# scanline-thin.net
KiCad netlist of a schematic drawn in Altium Designer
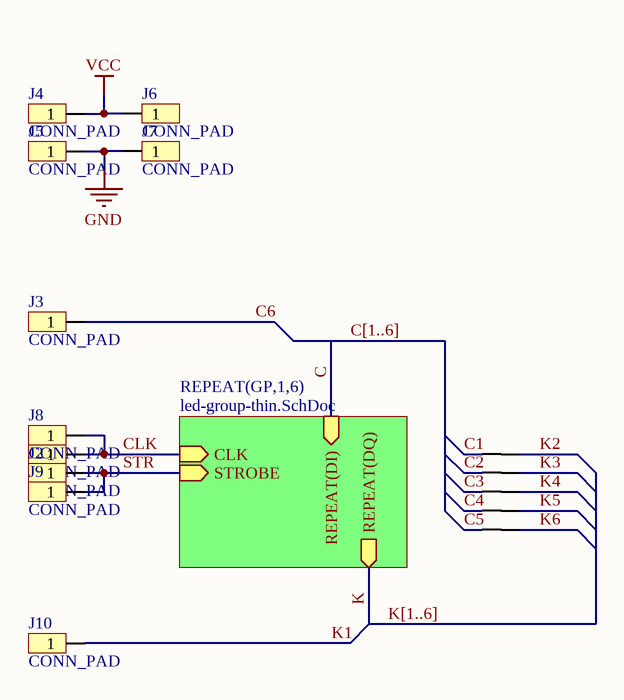
[diagram p0: scanline-thin.SchDoc]

(export (version "E")
  (design (tool "Eeschema 10.0.6"))
  (components
    (comp (ref "J1") (value "CONN_PAD") (libsource (lib "") (part "CONN_PAD_1")))
    (comp (ref "J2") (value "CONN_PAD") (libsource (lib "") (part "CONN_PAD_1")))
    (comp (ref "J3") (value "CONN_PAD") (libsource (lib "") (part "CONN_PAD_1")))
    (comp (ref "J4") (value "CONN_PAD") (libsource (lib "") (part "CONN_PAD_1")))
    (comp (ref "J5") (value "CONN_PAD") (libsource (lib "") (part "CONN_PAD_1")))
    (comp (ref "J6") (value "CONN_PAD") (libsource (lib "Components") (part "CONN_PAD")))
    (comp (ref "J7") (value "CONN_PAD") (libsource (lib "Components") (part "CONN_PAD")))
    (comp (ref "J8") (value "CONN_PAD") (libsource (lib "") (part "CONN_PAD_1")))
    (comp (ref "J9") (value "CONN_PAD") (libsource (lib "") (part "CONN_PAD_1")))
    (comp (ref "J10") (value "CONN_PAD") (libsource (lib "") (part "CONN_PAD_1")))
    (comp (ref "T2") (value "NETTIE") (footprint "NETTIE") (libsource (lib "Components") (part "NETTIE")))
    (comp (ref "T3") (value "NETTIE") (footprint "NETTIE") (libsource (lib "Components") (part "NETTIE")))
    (comp (ref "T4") (value "NETTIE") (footprint "NETTIE") (libsource (lib "Components") (part "NETTIE")))
    (comp (ref "T5") (value "NETTIE") (footprint "NETTIE") (libsource (lib "Components") (part "NETTIE")))
    (comp (ref "T6") (value "NETTIE") (footprint "NETTIE") (libsource (lib "Components") (part "NETTIE")))
  )
  (nets
    (net (code "2") (name "/C1") (class "Default")
      (node (ref "T2") (pin "1") (pinfunction "1_1") (pintype "bidirectional"))
    )
    (net (code "3") (name "/C2") (class "Default")
      (node (ref "T3") (pin "1") (pinfunction "1_1") (pintype "bidirectional"))
    )
    (net (code "4") (name "/C3") (class "Default")
      (node (ref "T4") (pin "1") (pinfunction "1_1") (pintype "bidirectional"))
    )
    (net (code "5") (name "/C4") (class "Default")
      (node (ref "T5") (pin "1") (pinfunction "1_1") (pintype "bidirectional"))
    )
    (net (code "6") (name "/C5") (class "Default")
      (node (ref "T6") (pin "1") (pinfunction "1_1") (pintype "bidirectional"))
    )
    (net (code "7") (name "/C6") (class "Default")
      (node (ref "J3") (pin "1") (pinfunction "1_1") (pintype "passive"))
    )
    (net (code "8") (name "/CLK") (class "Default")
      (node (ref "J1") (pin "1") (pinfunction "1_1") (pintype "passive"))
      (node (ref "J8") (pin "1") (pinfunction "1_1") (pintype "passive"))
    )
    (net (code "11") (name "/K1") (class "Default")
      (node (ref "J10") (pin "1") (pinfunction "1_1") (pintype "passive"))
    )
    (net (code "12") (name "/K2") (class "Default")
      (node (ref "T2") (pin "2") (pinfunction "2_2") (pintype "bidirectional"))
    )
    (net (code "13") (name "/K3") (class "Default")
      (node (ref "T3") (pin "2") (pinfunction "2_2") (pintype "bidirectional"))
    )
    (net (code "14") (name "/K4") (class "Default")
      (node (ref "T4") (pin "2") (pinfunction "2_2") (pintype "bidirectional"))
    )
    (net (code "15") (name "/K5") (class "Default")
      (node (ref "T5") (pin "2") (pinfunction "2_2") (pintype "bidirectional"))
    )
    (net (code "16") (name "/K6") (class "Default")
      (node (ref "T6") (pin "2") (pinfunction "2_2") (pintype "bidirectional"))
    )
    (net (code "18") (name "/STR") (class "Default")
      (node (ref "J2") (pin "1") (pinfunction "1_1") (pintype "passive"))
      (node (ref "J9") (pin "1") (pinfunction "1_1") (pintype "passive"))
    )
    (net (code "19") (name "GND") (class "Default")
      (node (ref "J5") (pin "1") (pinfunction "1_1") (pintype "passive"))
      (node (ref "J7") (pin "1") (pinfunction "1_1") (pintype "passive"))
    )
    (net (code "20") (name "VCC") (class "Default")
      (node (ref "J4") (pin "1") (pinfunction "1_1") (pintype "passive"))
      (node (ref "J6") (pin "1") (pinfunction "1_1") (pintype "passive"))
    )
  )
)
